# exam_elec.net
KiCad netlist of a schematic drawn in EAGLE
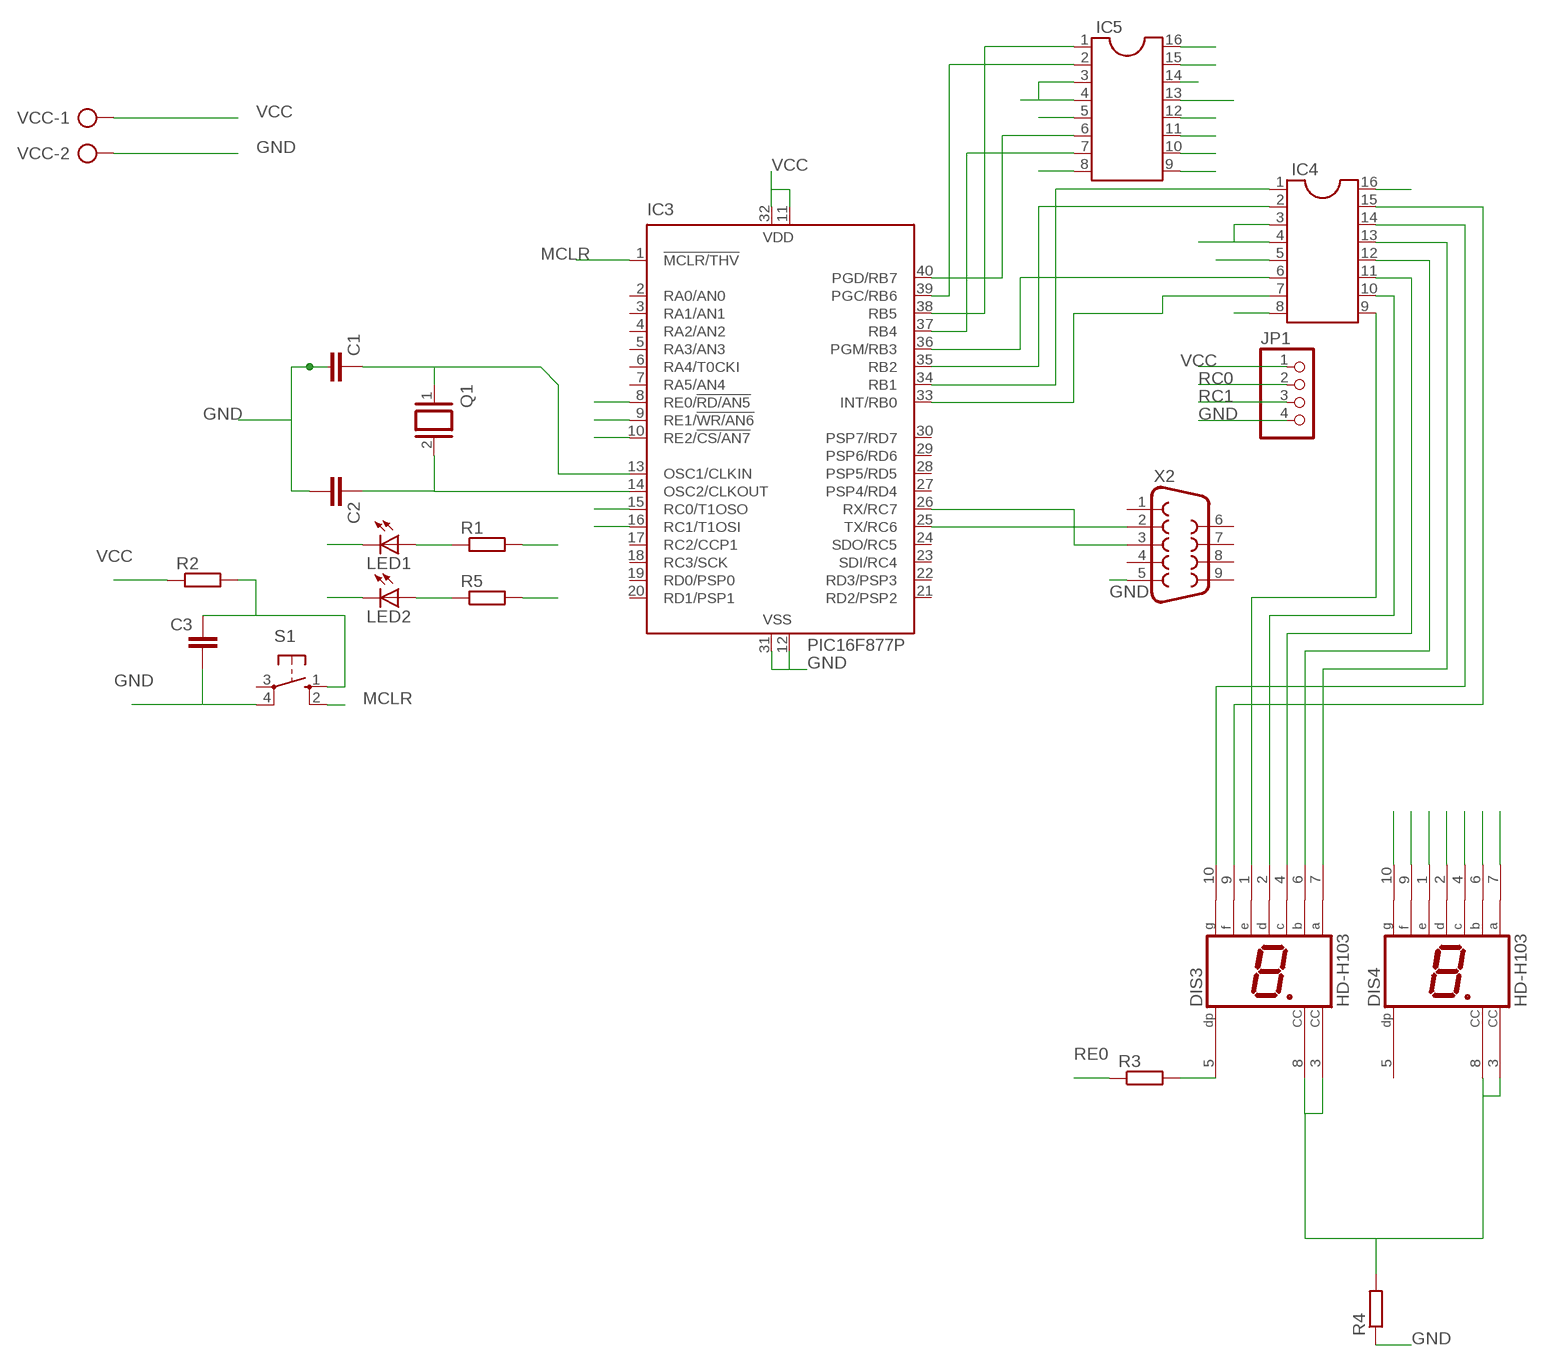
[diagram p0: schematic, sheet 1]

(export (version "E")
  (design (tool "Eeschema 10.0.6"))
  (components
    (comp (ref "C1")
      (value "C-EU025-025X050")
      (footprint "eagle-import:C025-025X050")
      (libsource (lib "eagle-import") (part "C-EU025-025X050"))
    )
    (comp (ref "C2")
      (value "C-EU025-025X050")
      (footprint "eagle-import:C025-025X050")
      (libsource (lib "eagle-import") (part "C-EU025-025X050"))
    )
    (comp (ref "C3")
      (value "C-EU025-025X050")
      (footprint "eagle-import:C025-025X050")
      (libsource (lib "eagle-import") (part "C-EU025-025X050"))
    )
    (comp (ref "DIS3")
      (value "HD-H103")
      (footprint "eagle-import:HDSP-M")
      (libsource (lib "eagle-import") (part "HD-H103"))
    )
    (comp (ref "DIS4")
      (value "HD-H103")
      (footprint "eagle-import:HDSP-M")
      (libsource (lib "eagle-import") (part "HD-H103"))
    )
    (comp (ref "IC3")
      (value "PIC16F877P")
      (footprint "eagle-import:DIL40")
      (fields (field (name "MF") "MICROCHIP") (field (name "MPN") "PIC16F877-04/P"))
      (libsource (lib "eagle-import") (part "PIC16F87P7"))
    )
    (comp (ref "IC4")
      (value "DIL16")
      (footprint "eagle-import:DIL16")
      (libsource (lib "eagle-import") (part "DIL16"))
    )
    (comp (ref "IC5")
      (value "DIL16")
      (footprint "eagle-import:DIL16")
      (libsource (lib "eagle-import") (part "DIL16"))
    )
    (comp (ref "JP1")
      (value "PINHD-1X4")
      (footprint "eagle-import:1X04")
      (libsource (lib "eagle-import") (part "PINHD-1X4"))
    )
    (comp (ref "LED1")
      (value "LED5MM")
      (footprint "eagle-import:LED5MM")
      (libsource (lib "eagle-import") (part "LED5MM"))
    )
    (comp (ref "LED2")
      (value "LED5MM")
      (footprint "eagle-import:LED5MM")
      (libsource (lib "eagle-import") (part "LED5MM"))
    )
    (comp (ref "Q1")
      (value "XTAL/S")
      (footprint "eagle-import:QS")
      (libsource (lib "eagle-import") (part "XTAL/S"))
    )
    (comp (ref "R1")
      (value "R-EU_0204/7")
      (footprint "eagle-import:0204_7")
      (libsource (lib "eagle-import") (part "R-EU_0204/7"))
    )
    (comp (ref "R2")
      (value "R-EU_0204/7")
      (footprint "eagle-import:0204_7")
      (libsource (lib "eagle-import") (part "R-EU_0204/7"))
    )
    (comp (ref "R3")
      (value "R-EU_0204/7")
      (footprint "eagle-import:0204_7")
      (libsource (lib "eagle-import") (part "R-EU_0204/7"))
    )
    (comp (ref "R4")
      (value "R-EU_0204/7")
      (footprint "eagle-import:0204_7")
      (libsource (lib "eagle-import") (part "R-EU_0204/7"))
    )
    (comp (ref "R5")
      (value "R-EU_0204/7")
      (footprint "eagle-import:0204_7")
      (libsource (lib "eagle-import") (part "R-EU_0204/7"))
    )
    (comp (ref "S1")
      (value "10-XX")
      (footprint "eagle-import:B3F-10XX")
      (fields (field (name "MPN") "B3F-1000"))
      (libsource (lib "eagle-import") (part "10-XX"))
    )
    (comp (ref "VCC")
      (value "AK300/2")
      (footprint "eagle-import:AK300_2")
      (libsource (lib "eagle-import") (part "AK300/2"))
    )
    (comp (ref "X2")
      (value "F09H")
      (footprint "eagle-import:F09H")
      (libsource (lib "eagle-import") (part "F09H"))
    )
  )
  (nets
    (net (code "1") (name "/A") (class "Default")
      (node (ref "DIS4") (pin "7") (pinfunction "A_7") (pintype "passive"))
      (node (ref "IC5") (pin "13") (pinfunction "13_13") (pintype "passive"))
    )
    (net (code "2") (name "/B") (class "Default")
      (node (ref "DIS4") (pin "6") (pinfunction "B_6") (pintype "passive"))
      (node (ref "IC5") (pin "12") (pinfunction "12_12") (pintype "passive"))
    )
    (net (code "3") (name "/C") (class "Default")
      (node (ref "DIS4") (pin "4") (pinfunction "C_4") (pintype "passive"))
      (node (ref "IC5") (pin "11") (pinfunction "11_11") (pintype "passive"))
    )
    (net (code "4") (name "/D") (class "Default")
      (node (ref "DIS4") (pin "2") (pinfunction "D_2") (pintype "passive"))
      (node (ref "IC5") (pin "10") (pinfunction "10_10") (pintype "passive"))
    )
    (net (code "5") (name "/E") (class "Default")
      (node (ref "DIS4") (pin "1") (pinfunction "E_1") (pintype "passive"))
      (node (ref "IC5") (pin "9") (pinfunction "9_9") (pintype "passive"))
    )
    (net (code "6") (name "/F") (class "Default")
      (node (ref "DIS4") (pin "9") (pinfunction "F_9") (pintype "passive"))
      (node (ref "IC5") (pin "15") (pinfunction "15_15") (pintype "passive"))
    )
    (net (code "7") (name "/G") (class "Default")
      (node (ref "DIS4") (pin "10") (pinfunction "G_10") (pintype "passive"))
      (node (ref "IC5") (pin "14") (pinfunction "14_14") (pintype "passive"))
    )
    (net (code "8") (name "/GND") (class "Default")
      (node (ref "C1") (pin "2") (pinfunction "2_2") (pintype "passive"))
      (node (ref "C2") (pin "2") (pinfunction "2_2") (pintype "passive"))
      (node (ref "C3") (pin "2") (pinfunction "2_2") (pintype "passive"))
      (node (ref "IC3") (pin "12") (pinfunction "VSS_12") (pintype "power_in"))
      (node (ref "IC3") (pin "31") (pinfunction "VSS_31") (pintype "power_in"))
      (node (ref "IC4") (pin "5") (pinfunction "5_5") (pintype "passive"))
      (node (ref "IC4") (pin "8") (pinfunction "8_8") (pintype "passive"))
      (node (ref "IC5") (pin "5") (pinfunction "5_5") (pintype "passive"))
      (node (ref "IC5") (pin "8") (pinfunction "8_8") (pintype "passive"))
      (node (ref "JP1") (pin "4") (pinfunction "4_4") (pintype "passive"))
      (node (ref "LED1") (pin "K") (pinfunction "C_K") (pintype "passive"))
      (node (ref "LED2") (pin "K") (pinfunction "C_K") (pintype "passive"))
      (node (ref "R4") (pin "1") (pinfunction "1_1") (pintype "passive"))
      (node (ref "S1") (pin "4") (pinfunction "P1_4") (pintype "passive"))
      (node (ref "VCC") (pin "2") (pinfunction "KL_2") (pintype "passive"))
      (node (ref "X2") (pin "5") (pinfunction "5_5") (pintype "passive"))
    )
    (net (code "9") (name "/MCLR") (class "Default")
      (node (ref "IC3") (pin "1") (pinfunction "~{MCLR/THV}_1") (pintype "input"))
      (node (ref "S1") (pin "2") (pinfunction "S1_2") (pintype "passive"))
    )
    (net (code "10") (name "/RC0") (class "Default")
      (node (ref "IC3") (pin "15") (pinfunction "RC0/T1OSO_15") (pintype "bidirectional"))
      (node (ref "JP1") (pin "2") (pinfunction "2_2") (pintype "passive"))
    )
    (net (code "11") (name "/RC1") (class "Default")
      (node (ref "IC3") (pin "16") (pinfunction "RC1/T1OSI_16") (pintype "bidirectional"))
      (node (ref "JP1") (pin "3") (pinfunction "3_3") (pintype "passive"))
    )
    (net (code "12") (name "/RE0") (class "Default")
      (node (ref "IC3") (pin "8") (pinfunction "RE0/~{RD/AN5}_8") (pintype "bidirectional"))
      (node (ref "R3") (pin "1") (pinfunction "1_1") (pintype "passive"))
    )
    (net (code "13") (name "/RE1") (class "Default")
      (node (ref "IC3") (pin "9") (pinfunction "RE1/~{WR/AN6}_9") (pintype "bidirectional"))
      (node (ref "R1") (pin "2") (pinfunction "2_2") (pintype "passive"))
    )
    (net (code "14") (name "/RE2") (class "Default")
      (node (ref "IC3") (pin "10") (pinfunction "RE2/~{CS/AN7}_10") (pintype "bidirectional"))
      (node (ref "R5") (pin "2") (pinfunction "2_2") (pintype "passive"))
    )
    (net (code "15") (name "/VCC") (class "Default")
      (node (ref "IC3") (pin "11") (pinfunction "VDD_11") (pintype "power_in"))
      (node (ref "IC3") (pin "32") (pinfunction "VDD_32") (pintype "power_in"))
      (node (ref "IC4") (pin "16") (pinfunction "16_16") (pintype "passive"))
      (node (ref "IC4") (pin "3") (pinfunction "3_3") (pintype "passive"))
      (node (ref "IC4") (pin "4") (pinfunction "4_4") (pintype "passive"))
      (node (ref "IC5") (pin "16") (pinfunction "16_16") (pintype "passive"))
      (node (ref "IC5") (pin "3") (pinfunction "3_3") (pintype "passive"))
      (node (ref "IC5") (pin "4") (pinfunction "4_4") (pintype "passive"))
      (node (ref "JP1") (pin "1") (pinfunction "1_1") (pintype "passive"))
      (node (ref "R2") (pin "1") (pinfunction "1_1") (pintype "passive"))
      (node (ref "VCC") (pin "1") (pinfunction "KL_1") (pintype "passive"))
    )
    (net (code "16") (name "Net-(DIS3-A)") (class "Default")
      (node (ref "DIS3") (pin "7") (pinfunction "A_7") (pintype "passive"))
      (node (ref "IC4") (pin "13") (pinfunction "13_13") (pintype "passive"))
    )
    (net (code "17") (name "Net-(DIS3-B)") (class "Default")
      (node (ref "DIS3") (pin "6") (pinfunction "B_6") (pintype "passive"))
      (node (ref "IC4") (pin "12") (pinfunction "12_12") (pintype "passive"))
    )
    (net (code "18") (name "Net-(DIS3-C)") (class "Default")
      (node (ref "DIS3") (pin "4") (pinfunction "C_4") (pintype "passive"))
      (node (ref "IC4") (pin "11") (pinfunction "11_11") (pintype "passive"))
    )
    (net (code "19") (name "Net-(DIS3-CC-Pad3)") (class "Default")
      (node (ref "DIS3") (pin "3") (pinfunction "CC_3") (pintype "passive"))
      (node (ref "DIS3") (pin "8") (pinfunction "CC_8") (pintype "passive"))
      (node (ref "DIS4") (pin "3") (pinfunction "CC_3") (pintype "passive"))
      (node (ref "DIS4") (pin "8") (pinfunction "CC_8") (pintype "passive"))
      (node (ref "R4") (pin "2") (pinfunction "2_2") (pintype "passive"))
    )
    (net (code "20") (name "Net-(DIS3-D)") (class "Default")
      (node (ref "DIS3") (pin "2") (pinfunction "D_2") (pintype "passive"))
      (node (ref "IC4") (pin "10") (pinfunction "10_10") (pintype "passive"))
    )
    (net (code "21") (name "Net-(DIS3-DP)") (class "Default")
      (node (ref "DIS3") (pin "5") (pinfunction "DP_5") (pintype "passive"))
      (node (ref "R3") (pin "2") (pinfunction "2_2") (pintype "passive"))
    )
    (net (code "22") (name "Net-(DIS3-E)") (class "Default")
      (node (ref "DIS3") (pin "1") (pinfunction "E_1") (pintype "passive"))
      (node (ref "IC4") (pin "9") (pinfunction "9_9") (pintype "passive"))
    )
    (net (code "23") (name "Net-(DIS3-F)") (class "Default")
      (node (ref "DIS3") (pin "9") (pinfunction "F_9") (pintype "passive"))
      (node (ref "IC4") (pin "15") (pinfunction "15_15") (pintype "passive"))
    )
    (net (code "24") (name "Net-(DIS3-G)") (class "Default")
      (node (ref "DIS3") (pin "10") (pinfunction "G_10") (pintype "passive"))
      (node (ref "IC4") (pin "14") (pinfunction "14_14") (pintype "passive"))
    )
    (net (code "25") (name "Net-(IC3-INT{slash}RB0)") (class "Default")
      (node (ref "IC3") (pin "33") (pinfunction "INT/RB0_33") (pintype "bidirectional"))
      (node (ref "IC4") (pin "7") (pinfunction "7_7") (pintype "passive"))
    )
    (net (code "26") (name "Net-(IC3-OSC1{slash}CLKIN)") (class "Default")
      (node (ref "C1") (pin "1") (pinfunction "1_1") (pintype "passive"))
      (node (ref "IC3") (pin "13") (pinfunction "OSC1/CLKIN_13") (pintype "input"))
      (node (ref "Q1") (pin "1") (pinfunction "1_1") (pintype "passive"))
    )
    (net (code "27") (name "Net-(IC3-OSC2{slash}CLKOUT)") (class "Default")
      (node (ref "C2") (pin "1") (pinfunction "1_1") (pintype "passive"))
      (node (ref "IC3") (pin "14") (pinfunction "OSC2/CLKOUT_14") (pintype "output"))
      (node (ref "Q1") (pin "2") (pinfunction "2_2") (pintype "passive"))
    )
    (net (code "28") (name "Net-(IC3-PGC{slash}RB6)") (class "Default")
      (node (ref "IC3") (pin "39") (pinfunction "PGC/RB6_39") (pintype "bidirectional"))
      (node (ref "IC5") (pin "2") (pinfunction "2_2") (pintype "passive"))
    )
    (net (code "29") (name "Net-(IC3-PGD{slash}RB7)") (class "Default")
      (node (ref "IC3") (pin "40") (pinfunction "PGD/RB7_40") (pintype "bidirectional"))
      (node (ref "IC5") (pin "6") (pinfunction "6_6") (pintype "passive"))
    )
    (net (code "30") (name "Net-(IC3-PGM{slash}RB3)") (class "Default")
      (node (ref "IC3") (pin "36") (pinfunction "PGM/RB3_36") (pintype "bidirectional"))
      (node (ref "IC4") (pin "6") (pinfunction "6_6") (pintype "passive"))
    )
    (net (code "31") (name "Net-(IC3-RB1)") (class "Default")
      (node (ref "IC3") (pin "34") (pinfunction "RB1_34") (pintype "bidirectional"))
      (node (ref "IC4") (pin "1") (pinfunction "1_1") (pintype "passive"))
    )
    (net (code "32") (name "Net-(IC3-RB2)") (class "Default")
      (node (ref "IC3") (pin "35") (pinfunction "RB2_35") (pintype "bidirectional"))
      (node (ref "IC4") (pin "2") (pinfunction "2_2") (pintype "passive"))
    )
    (net (code "33") (name "Net-(IC3-RB4)") (class "Default")
      (node (ref "IC3") (pin "37") (pinfunction "RB4_37") (pintype "bidirectional"))
      (node (ref "IC5") (pin "7") (pinfunction "7_7") (pintype "passive"))
    )
    (net (code "34") (name "Net-(IC3-RB5)") (class "Default")
      (node (ref "IC3") (pin "38") (pinfunction "RB5_38") (pintype "bidirectional"))
      (node (ref "IC5") (pin "1") (pinfunction "1_1") (pintype "passive"))
    )
    (net (code "35") (name "Net-(IC3-RX{slash}RC7)") (class "Default")
      (node (ref "IC3") (pin "26") (pinfunction "RX/RC7_26") (pintype "bidirectional"))
      (node (ref "X2") (pin "3") (pinfunction "3_3") (pintype "passive"))
    )
    (net (code "36") (name "Net-(IC3-TX{slash}RC6)") (class "Default")
      (node (ref "IC3") (pin "25") (pinfunction "TX/RC6_25") (pintype "bidirectional"))
      (node (ref "X2") (pin "2") (pinfunction "2_2") (pintype "passive"))
    )
    (net (code "37") (name "Net-(LED1-PadA)") (class "Default")
      (node (ref "LED1") (pin "A") (pinfunction "A_A") (pintype "passive"))
      (node (ref "R1") (pin "1") (pinfunction "1_1") (pintype "passive"))
    )
    (net (code "38") (name "Net-(LED2-PadA)") (class "Default")
      (node (ref "LED2") (pin "A") (pinfunction "A_A") (pintype "passive"))
      (node (ref "R5") (pin "1") (pinfunction "1_1") (pintype "passive"))
    )
    (net (code "39") (name "Net-(S1-S)") (class "Default")
      (node (ref "C3") (pin "1") (pinfunction "1_1") (pintype "passive"))
      (node (ref "R2") (pin "2") (pinfunction "2_2") (pintype "passive"))
      (node (ref "S1") (pin "1") (pinfunction "S_1") (pintype "passive"))
    )
    (net (code "40") (name "unconnected-(DIS4-DP-Pad5)") (class "Default")
      (node (ref "DIS4") (pin "5") (pinfunction "DP_5") (pintype "passive"))
    )
    (net (code "41") (name "unconnected-(IC3-PSP4{slash}RD4-Pad27)") (class "Default")
      (node (ref "IC3") (pin "27") (pinfunction "PSP4/RD4_27") (pintype "bidirectional"))
    )
    (net (code "42") (name "unconnected-(IC3-PSP5{slash}RD5-Pad28)") (class "Default")
      (node (ref "IC3") (pin "28") (pinfunction "PSP5/RD5_28") (pintype "bidirectional"))
    )
    (net (code "43") (name "unconnected-(IC3-PSP6{slash}RD6-Pad29)") (class "Default")
      (node (ref "IC3") (pin "29") (pinfunction "PSP6/RD6_29") (pintype "bidirectional"))
    )
    (net (code "44") (name "unconnected-(IC3-PSP7{slash}RD7-Pad30)") (class "Default")
      (node (ref "IC3") (pin "30") (pinfunction "PSP7/RD7_30") (pintype "bidirectional"))
    )
    (net (code "45") (name "unconnected-(IC3-RA0{slash}AN0-Pad2)") (class "Default")
      (node (ref "IC3") (pin "2") (pinfunction "RA0/AN0_2") (pintype "bidirectional"))
    )
    (net (code "46") (name "unconnected-(IC3-RA1{slash}AN1-Pad3)") (class "Default")
      (node (ref "IC3") (pin "3") (pinfunction "RA1/AN1_3") (pintype "bidirectional"))
    )
    (net (code "47") (name "unconnected-(IC3-RA2{slash}AN2-Pad4)") (class "Default")
      (node (ref "IC3") (pin "4") (pinfunction "RA2/AN2_4") (pintype "bidirectional"))
    )
    (net (code "48") (name "unconnected-(IC3-RA3{slash}AN3-Pad5)") (class "Default")
      (node (ref "IC3") (pin "5") (pinfunction "RA3/AN3_5") (pintype "bidirectional"))
    )
    (net (code "49") (name "unconnected-(IC3-RA4{slash}T0CKI-Pad6)") (class "Default")
      (node (ref "IC3") (pin "6") (pinfunction "RA4/T0CKI_6") (pintype "bidirectional"))
    )
    (net (code "50") (name "unconnected-(IC3-RA5{slash}AN4-Pad7)") (class "Default")
      (node (ref "IC3") (pin "7") (pinfunction "RA5/AN4_7") (pintype "bidirectional"))
    )
    (net (code "51") (name "unconnected-(IC3-RC2{slash}CCP1-Pad17)") (class "Default")
      (node (ref "IC3") (pin "17") (pinfunction "RC2/CCP1_17") (pintype "bidirectional"))
    )
    (net (code "52") (name "unconnected-(IC3-RC3{slash}SCK-Pad18)") (class "Default")
      (node (ref "IC3") (pin "18") (pinfunction "RC3/SCK_18") (pintype "bidirectional"))
    )
    (net (code "53") (name "unconnected-(IC3-RD0{slash}PSP0-Pad19)") (class "Default")
      (node (ref "IC3") (pin "19") (pinfunction "RD0/PSP0_19") (pintype "bidirectional"))
    )
    (net (code "54") (name "unconnected-(IC3-RD1{slash}PSP1-Pad20)") (class "Default")
      (node (ref "IC3") (pin "20") (pinfunction "RD1/PSP1_20") (pintype "bidirectional"))
    )
    (net (code "55") (name "unconnected-(IC3-RD2{slash}PSP2-Pad21)") (class "Default")
      (node (ref "IC3") (pin "21") (pinfunction "RD2/PSP2_21") (pintype "bidirectional"))
    )
    (net (code "56") (name "unconnected-(IC3-RD3{slash}PSP3-Pad22)") (class "Default")
      (node (ref "IC3") (pin "22") (pinfunction "RD3/PSP3_22") (pintype "bidirectional"))
    )
    (net (code "57") (name "unconnected-(IC3-SDI{slash}RC4-Pad23)") (class "Default")
      (node (ref "IC3") (pin "23") (pinfunction "SDI/RC4_23") (pintype "bidirectional"))
    )
    (net (code "58") (name "unconnected-(IC3-SDO{slash}RC5-Pad24)") (class "Default")
      (node (ref "IC3") (pin "24") (pinfunction "SDO/RC5_24") (pintype "bidirectional"))
    )
    (net (code "59") (name "unconnected-(S1-P-Pad3)") (class "Default")
      (node (ref "S1") (pin "3") (pinfunction "P_3") (pintype "passive"))
    )
    (net (code "60") (name "unconnected-(X2-Pad1)") (class "Default")
      (node (ref "X2") (pin "1") (pinfunction "1_1") (pintype "passive"))
    )
    (net (code "61") (name "unconnected-(X2-Pad4)") (class "Default")
      (node (ref "X2") (pin "4") (pinfunction "4_4") (pintype "passive"))
    )
    (net (code "62") (name "unconnected-(X2-Pad6)") (class "Default")
      (node (ref "X2") (pin "6") (pinfunction "6_6") (pintype "passive"))
    )
    (net (code "63") (name "unconnected-(X2-Pad7)") (class "Default")
      (node (ref "X2") (pin "7") (pinfunction "7_7") (pintype "passive"))
    )
    (net (code "64") (name "unconnected-(X2-Pad8)") (class "Default")
      (node (ref "X2") (pin "8") (pinfunction "8_8") (pintype "passive"))
    )
    (net (code "65") (name "unconnected-(X2-Pad9)") (class "Default")
      (node (ref "X2") (pin "9") (pinfunction "9_9") (pintype "passive"))
    )
  )
)
